# qcopter_fea_bb.net
KiCad netlist of a schematic drawn in EAGLE
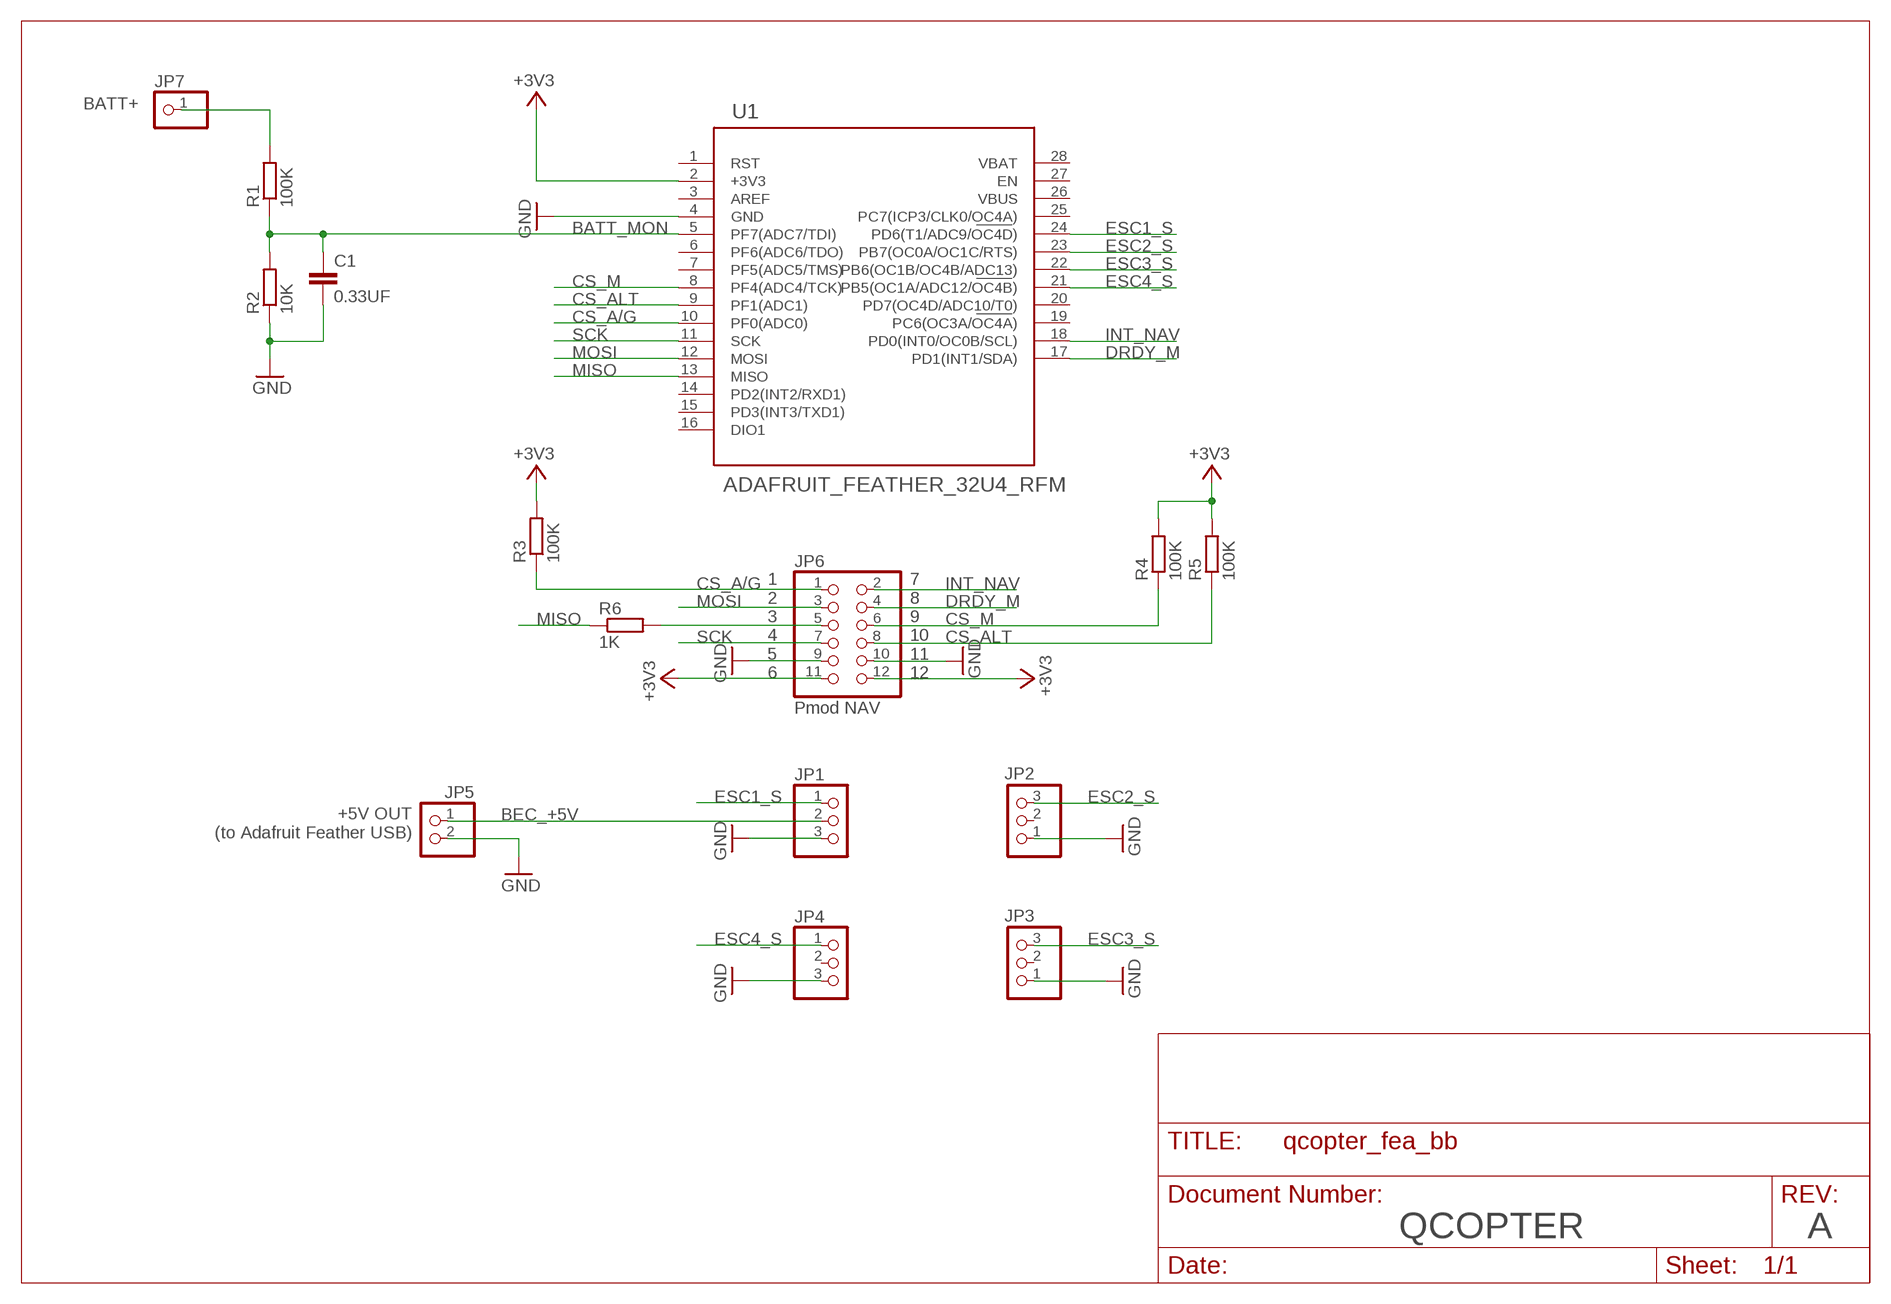
[diagram p0: schematic, sheet 1]

(export (version "E")
  (design (tool "Eeschema 10.0.6"))
  (components
    (comp (ref "C1")
      (value "0.33UF")
      (footprint "eagle-import:C025-025X050")
      (libsource (lib "eagle-import") (part "C-EU025-025X050"))
    )
    (comp (ref "JP1")
      (value "PINHD-1X3/90")
      (footprint "eagle-import:1X03_90")
      (libsource (lib "eagle-import") (part "PINHD-1X3/90"))
    )
    (comp (ref "JP2")
      (value "PINHD-1X3/90")
      (footprint "eagle-import:1X03_90")
      (libsource (lib "eagle-import") (part "PINHD-1X3/90"))
    )
    (comp (ref "JP3")
      (value "PINHD-1X3/90")
      (footprint "eagle-import:1X03_90")
      (libsource (lib "eagle-import") (part "PINHD-1X3/90"))
    )
    (comp (ref "JP4")
      (value "PINHD-1X3/90")
      (footprint "eagle-import:1X03_90")
      (libsource (lib "eagle-import") (part "PINHD-1X3/90"))
    )
    (comp (ref "JP5")
      (value "PINHD-1X2/90")
      (footprint "eagle-import:1X02_90")
      (libsource (lib "eagle-import") (part "PINHD-1X2/90"))
    )
    (comp (ref "JP6")
      (value "Pmod NAV")
      (footprint "eagle-import:2X06_90")
      (libsource (lib "eagle-import") (part "PINHD-2X6/90"))
    )
    (comp (ref "JP7")
      (value "PINHD-1X1")
      (footprint "eagle-import:1X01")
      (libsource (lib "eagle-import") (part "PINHD-1X1"))
    )
    (comp (ref "R1")
      (value "100K")
      (footprint "eagle-import:0207_10")
      (libsource (lib "eagle-import") (part "R-EU_0207/10"))
    )
    (comp (ref "R2")
      (value "10K")
      (footprint "eagle-import:0207_10")
      (libsource (lib "eagle-import") (part "R-EU_0207/10"))
    )
    (comp (ref "R3")
      (value "100K")
      (footprint "eagle-import:0207_10")
      (libsource (lib "eagle-import") (part "R-EU_0207/10"))
    )
    (comp (ref "R4")
      (value "100K")
      (footprint "eagle-import:0207_10")
      (libsource (lib "eagle-import") (part "R-EU_0207/10"))
    )
    (comp (ref "R5")
      (value "100K")
      (footprint "eagle-import:0207_10")
      (libsource (lib "eagle-import") (part "R-EU_0207/10"))
    )
    (comp (ref "R6")
      (value "1K")
      (footprint "eagle-import:0207_10")
      (libsource (lib "eagle-import") (part "R-EU_0207/10"))
    )
    (comp (ref "U1")
      (value "ADAFRUIT_FEATHER_32U4_RFM")
      (footprint "eagle-import:ADAFRUIT_FEATHER_32U4_RFM")
      (libsource (lib "eagle-import") (part "ADAFRUIT_FEATHER_32U4_RFM"))
    )
  )
  (nets
    (net (code "1") (name "+3V3") (class "Default")
      (node (ref "JP6") (pin "11") (pinfunction "11_11") (pintype "passive"))
      (node (ref "JP6") (pin "12") (pinfunction "12_12") (pintype "passive"))
      (node (ref "R3") (pin "2") (pinfunction "2_2") (pintype "passive"))
      (node (ref "R4") (pin "2") (pinfunction "2_2") (pintype "passive"))
      (node (ref "R5") (pin "2") (pinfunction "2_2") (pintype "passive"))
      (node (ref "U1") (pin "2") (pinfunction "+3V3_2") (pintype "bidirectional"))
    )
    (net (code "2") (name "/BATT+") (class "Default")
      (node (ref "JP7") (pin "1") (pinfunction "1_1") (pintype "passive"))
      (node (ref "R1") (pin "2") (pinfunction "2_2") (pintype "passive"))
    )
    (net (code "3") (name "/BATT_MON") (class "Default")
      (node (ref "C1") (pin "1") (pinfunction "1_1") (pintype "passive"))
      (node (ref "R1") (pin "1") (pinfunction "1_1") (pintype "passive"))
      (node (ref "R2") (pin "2") (pinfunction "2_2") (pintype "passive"))
      (node (ref "U1") (pin "5") (pinfunction "PF7(ADC7/TDI)_5") (pintype "bidirectional"))
    )
    (net (code "4") (name "/BEC_+5V") (class "Default")
      (node (ref "JP1") (pin "2") (pinfunction "2_2") (pintype "passive"))
      (node (ref "JP5") (pin "1") (pinfunction "1_1") (pintype "passive"))
    )
    (net (code "5") (name "/CS_ALT") (class "Default")
      (node (ref "JP6") (pin "8") (pinfunction "8_8") (pintype "passive"))
      (node (ref "R5") (pin "1") (pinfunction "1_1") (pintype "passive"))
      (node (ref "U1") (pin "9") (pinfunction "PF1(ADC1)_9") (pintype "bidirectional"))
    )
    (net (code "6") (name "/CS_A{slash}G") (class "Default")
      (node (ref "JP6") (pin "1") (pinfunction "1_1") (pintype "passive"))
      (node (ref "R3") (pin "1") (pinfunction "1_1") (pintype "passive"))
      (node (ref "U1") (pin "10") (pinfunction "PF0(ADC0)_10") (pintype "bidirectional"))
    )
    (net (code "7") (name "/CS_M") (class "Default")
      (node (ref "JP6") (pin "6") (pinfunction "6_6") (pintype "passive"))
      (node (ref "R4") (pin "1") (pinfunction "1_1") (pintype "passive"))
      (node (ref "U1") (pin "8") (pinfunction "PF4(ADC4/TCK)_8") (pintype "bidirectional"))
    )
    (net (code "8") (name "/DRDY_M") (class "Default")
      (node (ref "JP6") (pin "4") (pinfunction "4_4") (pintype "passive"))
      (node (ref "U1") (pin "17") (pinfunction "PD1(INT1/SDA)_17") (pintype "bidirectional"))
    )
    (net (code "9") (name "/ESC1_S") (class "Default")
      (node (ref "JP1") (pin "1") (pinfunction "1_1") (pintype "passive"))
      (node (ref "U1") (pin "24") (pinfunction "PD6(T1/ADC9/OC4D)_24") (pintype "bidirectional"))
    )
    (net (code "10") (name "/ESC2_S") (class "Default")
      (node (ref "JP2") (pin "3") (pinfunction "3_3") (pintype "passive"))
      (node (ref "U1") (pin "23") (pinfunction "PB7(OC0A/OC1C/RTS)_23") (pintype "bidirectional"))
    )
    (net (code "11") (name "/ESC3_S") (class "Default")
      (node (ref "JP3") (pin "3") (pinfunction "3_3") (pintype "passive"))
      (node (ref "U1") (pin "22") (pinfunction "PB6(OC1B/OC4B/ADC13)_22") (pintype "bidirectional"))
    )
    (net (code "12") (name "/ESC4_S") (class "Default")
      (node (ref "JP4") (pin "1") (pinfunction "1_1") (pintype "passive"))
      (node (ref "U1") (pin "21") (pinfunction "PB5(OC1A/ADC12/OC4B)_21") (pintype "bidirectional"))
    )
    (net (code "13") (name "/INT_NAV") (class "Default")
      (node (ref "JP6") (pin "2") (pinfunction "2_2") (pintype "passive"))
      (node (ref "U1") (pin "18") (pinfunction "PD0(INT0/OC0B/SCL)_18") (pintype "bidirectional"))
    )
    (net (code "14") (name "/MISO") (class "Default")
      (node (ref "R6") (pin "1") (pinfunction "1_1") (pintype "passive"))
      (node (ref "U1") (pin "13") (pinfunction "MISO_13") (pintype "bidirectional"))
    )
    (net (code "15") (name "/MOSI") (class "Default")
      (node (ref "JP6") (pin "3") (pinfunction "3_3") (pintype "passive"))
      (node (ref "U1") (pin "12") (pinfunction "MOSI_12") (pintype "bidirectional"))
    )
    (net (code "16") (name "/SCK") (class "Default")
      (node (ref "JP6") (pin "7") (pinfunction "7_7") (pintype "passive"))
      (node (ref "U1") (pin "11") (pinfunction "SCK_11") (pintype "bidirectional"))
    )
    (net (code "17") (name "GND") (class "Default")
      (node (ref "C1") (pin "2") (pinfunction "2_2") (pintype "passive"))
      (node (ref "JP1") (pin "3") (pinfunction "3_3") (pintype "passive"))
      (node (ref "JP2") (pin "1") (pinfunction "1_1") (pintype "passive"))
      (node (ref "JP3") (pin "1") (pinfunction "1_1") (pintype "passive"))
      (node (ref "JP4") (pin "3") (pinfunction "3_3") (pintype "passive"))
      (node (ref "JP5") (pin "2") (pinfunction "2_2") (pintype "passive"))
      (node (ref "JP6") (pin "10") (pinfunction "10_10") (pintype "passive"))
      (node (ref "JP6") (pin "9") (pinfunction "9_9") (pintype "passive"))
      (node (ref "R2") (pin "1") (pinfunction "1_1") (pintype "passive"))
      (node (ref "U1") (pin "4") (pinfunction "GND_4") (pintype "bidirectional"))
    )
    (net (code "18") (name "Net-(JP6-Pad5)") (class "Default")
      (node (ref "JP6") (pin "5") (pinfunction "5_5") (pintype "passive"))
      (node (ref "R6") (pin "2") (pinfunction "2_2") (pintype "passive"))
    )
    (net (code "19") (name "unconnected-(JP2-Pad2)") (class "Default")
      (node (ref "JP2") (pin "2") (pinfunction "2_2") (pintype "passive"))
    )
    (net (code "20") (name "unconnected-(JP3-Pad2)") (class "Default")
      (node (ref "JP3") (pin "2") (pinfunction "2_2") (pintype "passive"))
    )
    (net (code "21") (name "unconnected-(JP4-Pad2)") (class "Default")
      (node (ref "JP4") (pin "2") (pinfunction "2_2") (pintype "passive"))
    )
    (net (code "22") (name "unconnected-(U1-AREF-Pad3)") (class "Default")
      (node (ref "U1") (pin "3") (pinfunction "AREF_3") (pintype "bidirectional"))
    )
    (net (code "23") (name "unconnected-(U1-DIO1-Pad16)") (class "Default")
      (node (ref "U1") (pin "16") (pinfunction "DIO1_16") (pintype "bidirectional"))
    )
    (net (code "24") (name "unconnected-(U1-EN-Pad27)") (class "Default")
      (node (ref "U1") (pin "27") (pinfunction "EN_27") (pintype "bidirectional"))
    )
    (net (code "25") (name "unconnected-(U1-PC6(OC3A{slash}OC4A)-Pad19)") (class "Default")
      (node (ref "U1") (pin "19") (pinfunction "PC6(OC3A/OC4A)_19") (pintype "bidirectional"))
    )
    (net (code "26") (name "unconnected-(U1-PC7(ICP3{slash}CLK0{slash}OC4A)-Pad25)") (class "Default")
      (node (ref "U1") (pin "25") (pinfunction "PC7(ICP3/CLK0/OC4A)_25") (pintype "bidirectional"))
    )
    (net (code "27") (name "unconnected-(U1-PD2(INT2{slash}RXD1)-Pad14)") (class "Default")
      (node (ref "U1") (pin "14") (pinfunction "PD2(INT2/RXD1)_14") (pintype "bidirectional"))
    )
    (net (code "28") (name "unconnected-(U1-PD3(INT3{slash}TXD1)-Pad15)") (class "Default")
      (node (ref "U1") (pin "15") (pinfunction "PD3(INT3/TXD1)_15") (pintype "bidirectional"))
    )
    (net (code "29") (name "unconnected-(U1-PD7(OC4D{slash}ADC10{slash}T0)-Pad20)") (class "Default")
      (node (ref "U1") (pin "20") (pinfunction "PD7(OC4D/ADC10/T0)_20") (pintype "bidirectional"))
    )
    (net (code "30") (name "unconnected-(U1-PF5(ADC5{slash}TMS)-Pad7)") (class "Default")
      (node (ref "U1") (pin "7") (pinfunction "PF5(ADC5/TMS)_7") (pintype "bidirectional"))
    )
    (net (code "31") (name "unconnected-(U1-PF6(ADC6{slash}TDO)-Pad6)") (class "Default")
      (node (ref "U1") (pin "6") (pinfunction "PF6(ADC6/TDO)_6") (pintype "bidirectional"))
    )
    (net (code "32") (name "unconnected-(U1-RST-Pad1)") (class "Default")
      (node (ref "U1") (pin "1") (pinfunction "RST_1") (pintype "bidirectional"))
    )
    (net (code "33") (name "unconnected-(U1-VBAT-Pad28)") (class "Default")
      (node (ref "U1") (pin "28") (pinfunction "VBAT_28") (pintype "bidirectional"))
    )
    (net (code "34") (name "unconnected-(U1-VBUS-Pad26)") (class "Default")
      (node (ref "U1") (pin "26") (pinfunction "VBUS_26") (pintype "bidirectional"))
    )
  )
)
